# CON_ETH.net
KiCad netlist of a schematic drawn in Altium Designer
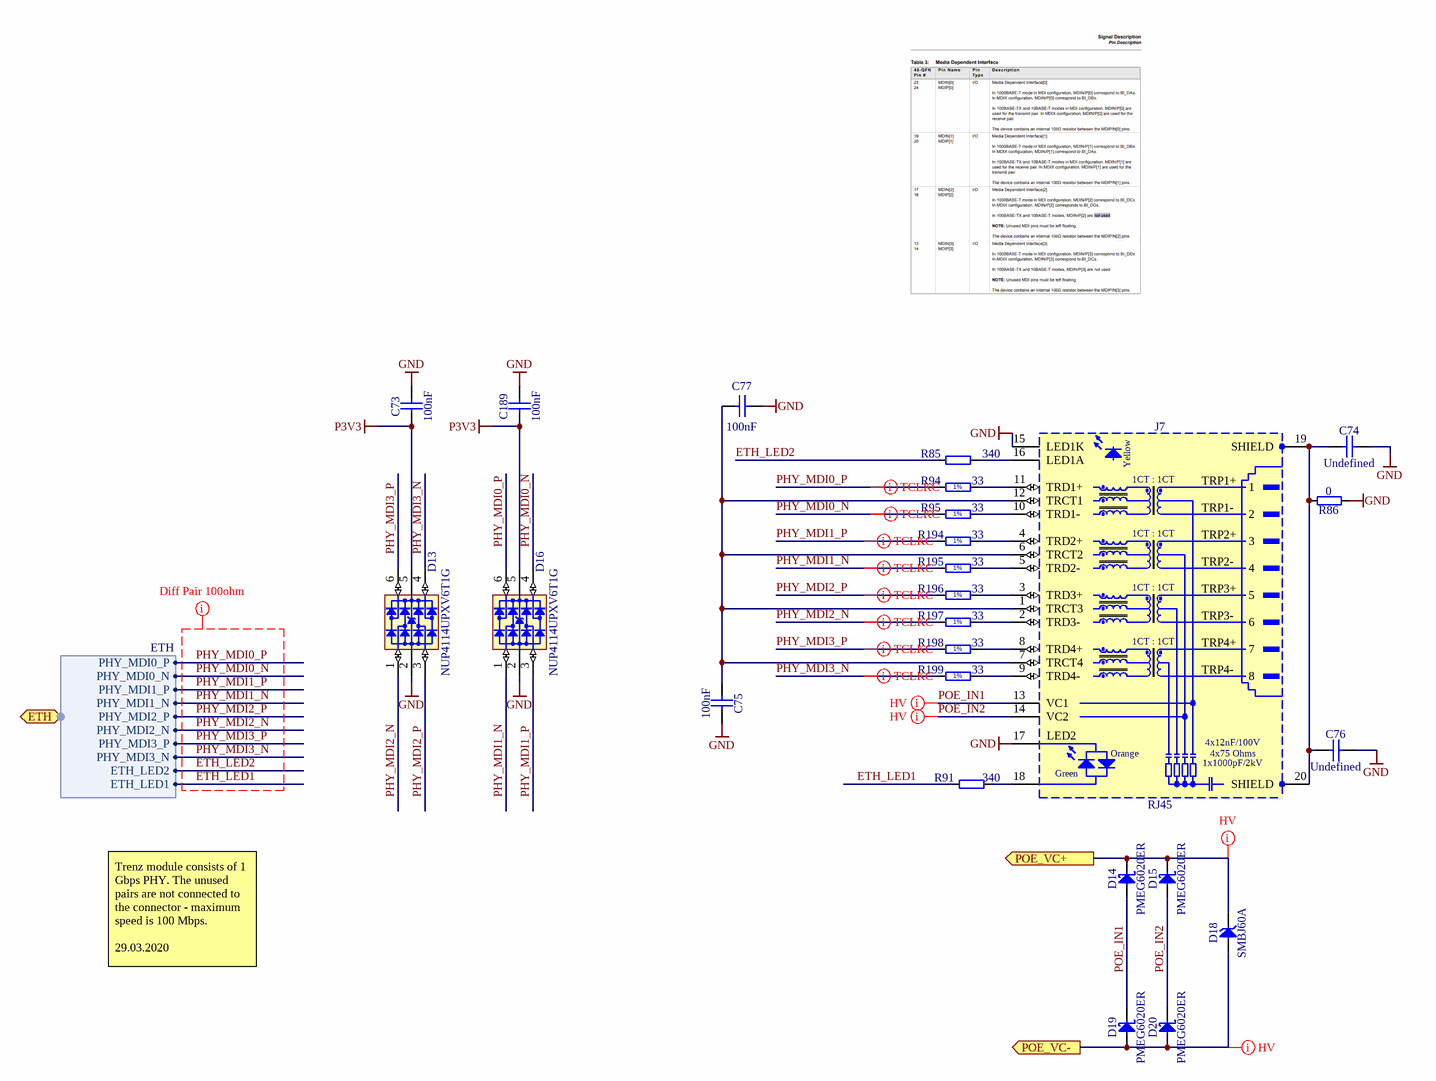
[diagram p0: CON_ETH.SchDoc]

(export (version "E")
  (design (tool "Eeschema 10.0.6"))
  (components
    (comp (ref "C73")
      (value "100nF")
      (footprint "CAPC1005X55N")
      (description "Non-polarised capacitor")
      (fields
        (field (name "PART NUMBER") "CC0402_100NF_16V_10%_X5R")
        (field (name "VOLTAGE") "16V")
        (field (name "AUTHOR") "CERN DEM JLC")
      )
      (libsource (lib "Capacitors") (part "Capacitor - non polarized"))
    )
    (comp (ref "C74")
      (value "Undefined")
      (footprint "CAPC1608X90N")
      (description "Non-polarised capacitor")
      (fields (field (name "PART NUMBER") "CC0603_NO-VALUE") (field (name "AUTHOR") "CERN DEM MR"))
      (libsource (lib "Capacitors") (part "Capacitor - non polarized"))
    )
    (comp (ref "C75")
      (value "100nF")
      (footprint "CAPC1005X55N")
      (description "Non-polarised capacitor")
      (fields
        (field (name "PART NUMBER") "CC0402_100NF_16V_10%_X5R")
        (field (name "VOLTAGE") "16V")
        (field (name "AUTHOR") "CERN DEM JLC")
      )
      (libsource (lib "Capacitors") (part "Capacitor - non polarized"))
    )
    (comp (ref "C76")
      (value "Undefined")
      (footprint "CAPC1608X90N")
      (description "Non-polarised capacitor")
      (fields (field (name "PART NUMBER") "CC0603_NO-VALUE") (field (name "AUTHOR") "CERN DEM MR"))
      (libsource (lib "Capacitors") (part "Capacitor - non polarized"))
    )
    (comp (ref "C77")
      (value "100nF")
      (footprint "CAPC1005X55N")
      (description "Non-polarised capacitor")
      (fields
        (field (name "PART NUMBER") "CC0402_100NF_16V_10%_X5R")
        (field (name "VOLTAGE") "16V")
        (field (name "AUTHOR") "CERN DEM JLC")
      )
      (libsource (lib "Capacitors") (part "Capacitor - non polarized"))
    )
    (comp (ref "C189")
      (value "100nF")
      (footprint "CAPC1005X55N")
      (description "Non-polarised capacitor")
      (fields
        (field (name "PART NUMBER") "CC0402_100NF_16V_10%_X5R")
        (field (name "VOLTAGE") "16V")
        (field (name "AUTHOR") "CERN DEM JLC")
      )
      (libsource (lib "Capacitors") (part "Capacitor - non polarized"))
    )
    (comp (ref "D13")
      (value "NUP4114UPXV6T1G")
      (footprint "SOTFL50P160X60-6N")
      (fields
        (field (name "VOLTAGE") "5.5V")
        (field (name "MANUFACTURER") "ON SEMICONDUCTOR")
        (field (name "AUTHOR") "CERN DEM JLC")
      )
      (libsource (lib "ICs And Semiconductors") (part "NUP4114"))
    )
    (comp (ref "D14")
      (value "PMEG6020ER")
      (footprint "SODFL3517X110N")
      (description "Schottky Diode")
      (fields
        (field (name "VOLTAGE") "60V")
        (field (name "POWER") "2A")
        (field (name "AUTHOR") "CERN DEM JMW")
      )
      (libsource (lib "ICs And Semiconductors") (part "Diode Schottky"))
    )
    (comp (ref "D15")
      (value "PMEG6020ER")
      (footprint "SODFL3517X110N")
      (description "Schottky Diode")
      (fields
        (field (name "VOLTAGE") "60V")
        (field (name "POWER") "2A")
        (field (name "AUTHOR") "CERN DEM JMW")
      )
      (libsource (lib "ICs And Semiconductors") (part "Diode Schottky"))
    )
    (comp (ref "D16")
      (value "NUP4114UPXV6T1G")
      (footprint "SOTFL50P160X60-6N")
      (fields
        (field (name "VOLTAGE") "5.5V")
        (field (name "MANUFACTURER") "ON SEMICONDUCTOR")
        (field (name "AUTHOR") "CERN DEM JLC")
      )
      (libsource (lib "ICs And Semiconductors") (part "NUP4114"))
    )
    (comp (ref "D18")
      (value "SMBJ60A")
      (footprint "DIOM5336X265N")
      (description "Zener Diode")
      (fields
        (field (name "VOLTAGE") "60V")
        (field (name "POWER") "600W")
        (field (name "AUTHOR") "CERN DEM JLC")
      )
      (libsource (lib "ICs And Semiconductors") (part "Diode Zener"))
    )
    (comp (ref "D19")
      (value "PMEG6020ER")
      (footprint "SODFL3517X110N")
      (description "Schottky Diode")
      (fields
        (field (name "VOLTAGE") "60V")
        (field (name "POWER") "2A")
        (field (name "AUTHOR") "CERN DEM JMW")
      )
      (libsource (lib "ICs And Semiconductors") (part "Diode Schottky"))
    )
    (comp (ref "D20")
      (value "PMEG6020ER")
      (footprint "SODFL3517X110N")
      (description "Schottky Diode")
      (fields
        (field (name "VOLTAGE") "60V")
        (field (name "POWER") "2A")
        (field (name "AUTHOR") "CERN DEM JMW")
      )
      (libsource (lib "ICs And Semiconductors") (part "Diode Schottky"))
    )
    (comp (ref "J7")
      (value "RJ45")
      (footprint "BEL_0826-1X1T-80-F")
      (description "MagJack 1000BaseT, PoE+, 1X1, OG/Y, Tab Up, RoHS")
      (fields
        (field (name "PART NUMBER") "BELFUSE_0826-1X1T-80-F")
        (field (name "MANUFACTURER") "BEL MAGNETIC SOLUTIONS")
        (field (name "AUTHOR") "CERN DEM JLC")
      )
      (libsource (lib "Connectors") (part "BEL_0826-1X1T-80-F"))
    )
    (comp (ref "R85")
      (value "340")
      (footprint "RESC1608X55N")
      (description "Resistor - 0.1%")
      (fields
        (field (name "PART NUMBER") "R0603_340R_0.1%_0.063W_10PPM")
        (field (name "POWER") "0.063W")
        (field (name "AUTHOR") "CERN DEM JLC")
      )
      (libsource (lib "Resistors") (part "Resistor - 0.1%"))
    )
    (comp (ref "R86")
      (value "0")
      (footprint "RESC1005X40N")
      (description "Resistor")
      (fields
        (field (name "PART NUMBER") "R0402_0R_JUMPER")
        (field (name "MANUFACTURER") "GENERIC")
        (field (name "AUTHOR") "CERN DEM JLC")
      )
      (libsource (lib "Resistors") (part "Resistor"))
    )
    (comp (ref "R91")
      (value "340")
      (footprint "RESC1608X55N")
      (description "Resistor - 0.1%")
      (fields
        (field (name "PART NUMBER") "R0603_340R_0.1%_0.063W_10PPM")
        (field (name "POWER") "0.063W")
        (field (name "AUTHOR") "CERN DEM JLC")
      )
      (libsource (lib "Resistors") (part "Resistor - 0.1%"))
    )
    (comp (ref "R94")
      (value "33")
      (footprint "RESC1005X40N")
      (description "Resistor - 1%")
      (fields
        (field (name "PART NUMBER") "R0402_33R_1%_0.0625W_100PPM")
        (field (name "POWER") "0.0625W")
        (field (name "AUTHOR") "CERN DEM JLC")
      )
      (libsource (lib "Resistors") (part "Resistor - 1%"))
    )
    (comp (ref "R95")
      (value "33")
      (footprint "RESC1005X40N")
      (description "Resistor - 1%")
      (fields
        (field (name "PART NUMBER") "R0402_33R_1%_0.0625W_100PPM")
        (field (name "POWER") "0.0625W")
        (field (name "AUTHOR") "CERN DEM JLC")
      )
      (libsource (lib "Resistors") (part "Resistor - 1%"))
    )
    (comp (ref "R194")
      (value "33")
      (footprint "RESC1005X40N")
      (description "Resistor - 1%")
      (fields
        (field (name "PART NUMBER") "R0402_33R_1%_0.0625W_100PPM")
        (field (name "POWER") "0.0625W")
        (field (name "AUTHOR") "CERN DEM JLC")
      )
      (libsource (lib "Resistors") (part "Resistor - 1%"))
    )
    (comp (ref "R195")
      (value "33")
      (footprint "RESC1005X40N")
      (description "Resistor - 1%")
      (fields
        (field (name "PART NUMBER") "R0402_33R_1%_0.0625W_100PPM")
        (field (name "POWER") "0.0625W")
        (field (name "AUTHOR") "CERN DEM JLC")
      )
      (libsource (lib "Resistors") (part "Resistor - 1%"))
    )
    (comp (ref "R196")
      (value "33")
      (footprint "RESC1005X40N")
      (description "Resistor - 1%")
      (fields
        (field (name "PART NUMBER") "R0402_33R_1%_0.0625W_100PPM")
        (field (name "POWER") "0.0625W")
        (field (name "AUTHOR") "CERN DEM JLC")
      )
      (libsource (lib "Resistors") (part "Resistor - 1%"))
    )
    (comp (ref "R197")
      (value "33")
      (footprint "RESC1005X40N")
      (description "Resistor - 1%")
      (fields
        (field (name "PART NUMBER") "R0402_33R_1%_0.0625W_100PPM")
        (field (name "POWER") "0.0625W")
        (field (name "AUTHOR") "CERN DEM JLC")
      )
      (libsource (lib "Resistors") (part "Resistor - 1%"))
    )
    (comp (ref "R198")
      (value "33")
      (footprint "RESC1005X40N")
      (description "Resistor - 1%")
      (fields
        (field (name "PART NUMBER") "R0402_33R_1%_0.0625W_100PPM")
        (field (name "POWER") "0.0625W")
        (field (name "AUTHOR") "CERN DEM JLC")
      )
      (libsource (lib "Resistors") (part "Resistor - 1%"))
    )
    (comp (ref "R199")
      (value "33")
      (footprint "RESC1005X40N")
      (description "Resistor - 1%")
      (fields
        (field (name "PART NUMBER") "R0402_33R_1%_0.0625W_100PPM")
        (field (name "POWER") "0.0625W")
        (field (name "AUTHOR") "CERN DEM JLC")
      )
      (libsource (lib "Resistors") (part "Resistor - 1%"))
    )
  )
  (nets
    (net (code "2") (name "/ETH_LED1") (class "Default")
      (node (ref "R91") (pin "1") (pinfunction "1_1") (pintype "passive"))
    )
    (net (code "3") (name "/ETH_LED2") (class "Default")
      (node (ref "R85") (pin "1") (pinfunction "1_1") (pintype "passive"))
    )
    (net (code "4") (name "/PHY_MDI0_N") (class "Default")
      (node (ref "D16") (pin "4") (pinfunction "I/O3_4") (pintype "bidirectional"))
      (node (ref "R95") (pin "1") (pinfunction "1_1") (pintype "passive"))
    )
    (net (code "5") (name "/PHY_MDI0_P") (class "Default")
      (node (ref "D16") (pin "6") (pinfunction "I/O4_6") (pintype "bidirectional"))
      (node (ref "R94") (pin "1") (pinfunction "1_1") (pintype "passive"))
    )
    (net (code "6") (name "/PHY_MDI1_N") (class "Default")
      (node (ref "D16") (pin "1") (pinfunction "I/O1_1") (pintype "bidirectional"))
      (node (ref "R195") (pin "1") (pinfunction "1_1") (pintype "passive"))
    )
    (net (code "7") (name "/PHY_MDI1_P") (class "Default")
      (node (ref "D16") (pin "3") (pinfunction "I/O2_3") (pintype "bidirectional"))
      (node (ref "R194") (pin "1") (pinfunction "1_1") (pintype "passive"))
    )
    (net (code "8") (name "/PHY_MDI2_N") (class "Default")
      (node (ref "D13") (pin "1") (pinfunction "I/O1_1") (pintype "bidirectional"))
      (node (ref "R197") (pin "1") (pinfunction "1_1") (pintype "passive"))
    )
    (net (code "9") (name "/PHY_MDI2_P") (class "Default")
      (node (ref "D13") (pin "3") (pinfunction "I/O2_3") (pintype "bidirectional"))
      (node (ref "R196") (pin "1") (pinfunction "1_1") (pintype "passive"))
    )
    (net (code "10") (name "/PHY_MDI3_N") (class "Default")
      (node (ref "D13") (pin "4") (pinfunction "I/O3_4") (pintype "bidirectional"))
      (node (ref "R199") (pin "1") (pinfunction "1_1") (pintype "passive"))
    )
    (net (code "11") (name "/PHY_MDI3_P") (class "Default")
      (node (ref "D13") (pin "6") (pinfunction "I/O4_6") (pintype "bidirectional"))
      (node (ref "R198") (pin "1") (pinfunction "1_1") (pintype "passive"))
    )
    (net (code "12") (name "/POE_IN1") (class "Default")
      (node (ref "D14") (pin "2") (pinfunction "A_2") (pintype "passive"))
      (node (ref "D19") (pin "1") (pinfunction "C_1") (pintype "passive"))
      (node (ref "J7") (pin "13") (pinfunction "VC1_13") (pintype "passive"))
    )
    (net (code "13") (name "/POE_IN2") (class "Default")
      (node (ref "D15") (pin "2") (pinfunction "A_2") (pintype "passive"))
      (node (ref "D20") (pin "1") (pinfunction "C_1") (pintype "passive"))
      (node (ref "J7") (pin "14") (pinfunction "VC2_14") (pintype "passive"))
    )
    (net (code "14") (name "/POE_VC+") (class "Default")
      (node (ref "D14") (pin "1") (pinfunction "C_1") (pintype "passive"))
      (node (ref "D15") (pin "1") (pinfunction "C_1") (pintype "passive"))
      (node (ref "D18") (pin "1") (pinfunction "C_1") (pintype "passive"))
    )
    (net (code "15") (name "/POE_VC-") (class "Default")
      (node (ref "D18") (pin "2") (pinfunction "A_2") (pintype "passive"))
      (node (ref "D19") (pin "2") (pinfunction "A_2") (pintype "passive"))
      (node (ref "D20") (pin "2") (pinfunction "A_2") (pintype "passive"))
    )
    (net (code "17") (name "GND") (class "Default")
      (node (ref "C189") (pin "2") (pinfunction "2_2") (pintype "passive"))
      (node (ref "C73") (pin "2") (pinfunction "2_2") (pintype "passive"))
      (node (ref "C74") (pin "2") (pinfunction "2_2") (pintype "passive"))
      (node (ref "C75") (pin "1") (pinfunction "1_1") (pintype "passive"))
      (node (ref "C76") (pin "2") (pinfunction "2_2") (pintype "passive"))
      (node (ref "C77") (pin "2") (pinfunction "2_2") (pintype "passive"))
      (node (ref "D13") (pin "2") (pinfunction "GND_2") (pintype "power_in"))
      (node (ref "D16") (pin "2") (pinfunction "GND_2") (pintype "power_in"))
      (node (ref "J7") (pin "15") (pinfunction "LED1K_15") (pintype "passive"))
      (node (ref "J7") (pin "17") (pinfunction "LED2_17") (pintype "passive"))
      (node (ref "R86") (pin "1") (pinfunction "1_1") (pintype "passive"))
    )
    (net (code "18") (name "Net-(C74-Pad1)") (class "Default")
      (node (ref "C74") (pin "1") (pinfunction "1_1") (pintype "passive"))
      (node (ref "C76") (pin "1") (pinfunction "1_1") (pintype "passive"))
      (node (ref "J7") (pin "19") (pinfunction "SHIELD_19") (pintype "power_in"))
      (node (ref "J7") (pin "20") (pinfunction "SHIELD_20") (pintype "power_in"))
      (node (ref "R86") (pin "2") (pinfunction "2_2") (pintype "passive"))
    )
    (net (code "19") (name "Net-(J7-LED1A)") (class "Default")
      (node (ref "J7") (pin "16") (pinfunction "LED1A_16") (pintype "passive"))
      (node (ref "R85") (pin "2") (pinfunction "2_2") (pintype "passive"))
    )
    (net (code "20") (name "Net-(J7-LED2-Pad18)") (class "Default")
      (node (ref "J7") (pin "18") (pinfunction "LED2_18") (pintype "passive"))
      (node (ref "R91") (pin "2") (pinfunction "2_2") (pintype "passive"))
    )
    (net (code "21") (name "Net-(J7-TRCT1)") (class "Default")
      (node (ref "C75") (pin "2") (pinfunction "2_2") (pintype "passive"))
      (node (ref "C77") (pin "1") (pinfunction "1_1") (pintype "passive"))
      (node (ref "J7") (pin "1") (pinfunction "TRCT3_1") (pintype "bidirectional"))
      (node (ref "J7") (pin "12") (pinfunction "TRCT1_12") (pintype "bidirectional"))
      (node (ref "J7") (pin "6") (pinfunction "TRCT2_6") (pintype "bidirectional"))
      (node (ref "J7") (pin "7") (pinfunction "TRCT4_7") (pintype "bidirectional"))
    )
    (net (code "22") (name "Net-(J7-TRD1+)") (class "Default")
      (node (ref "J7") (pin "11") (pinfunction "TRD1+_11") (pintype "bidirectional"))
      (node (ref "R94") (pin "2") (pinfunction "2_2") (pintype "passive"))
    )
    (net (code "23") (name "Net-(J7-TRD1-)") (class "Default")
      (node (ref "J7") (pin "10") (pinfunction "TRD1-_10") (pintype "bidirectional"))
      (node (ref "R95") (pin "2") (pinfunction "2_2") (pintype "passive"))
    )
    (net (code "24") (name "Net-(J7-TRD2+)") (class "Default")
      (node (ref "J7") (pin "4") (pinfunction "TRD2+_4") (pintype "bidirectional"))
      (node (ref "R194") (pin "2") (pinfunction "2_2") (pintype "passive"))
    )
    (net (code "25") (name "Net-(J7-TRD2-)") (class "Default")
      (node (ref "J7") (pin "5") (pinfunction "TRD2-_5") (pintype "bidirectional"))
      (node (ref "R195") (pin "2") (pinfunction "2_2") (pintype "passive"))
    )
    (net (code "26") (name "Net-(J7-TRD3+)") (class "Default")
      (node (ref "J7") (pin "3") (pinfunction "TRD3+_3") (pintype "bidirectional"))
      (node (ref "R196") (pin "2") (pinfunction "2_2") (pintype "passive"))
    )
    (net (code "27") (name "Net-(J7-TRD3-)") (class "Default")
      (node (ref "J7") (pin "2") (pinfunction "TRD3-_2") (pintype "bidirectional"))
      (node (ref "R197") (pin "2") (pinfunction "2_2") (pintype "passive"))
    )
    (net (code "28") (name "Net-(J7-TRD4+)") (class "Default")
      (node (ref "J7") (pin "8") (pinfunction "TRD4+_8") (pintype "bidirectional"))
      (node (ref "R198") (pin "2") (pinfunction "2_2") (pintype "passive"))
    )
    (net (code "29") (name "Net-(J7-TRD4-)") (class "Default")
      (node (ref "J7") (pin "9") (pinfunction "TRD4-_9") (pintype "bidirectional"))
      (node (ref "R199") (pin "2") (pinfunction "2_2") (pintype "passive"))
    )
    (net (code "30") (name "P3V3") (class "Default")
      (node (ref "C189") (pin "1") (pinfunction "1_1") (pintype "passive"))
      (node (ref "C73") (pin "1") (pinfunction "1_1") (pintype "passive"))
      (node (ref "D13") (pin "5") (pinfunction "VBUS_5") (pintype "power_in"))
      (node (ref "D16") (pin "5") (pinfunction "VBUS_5") (pintype "power_in"))
    )
  )
)
